# RPi-HAT_BUS-Controller_V0_9b.net
KiCad netlist of a schematic drawn in EAGLE
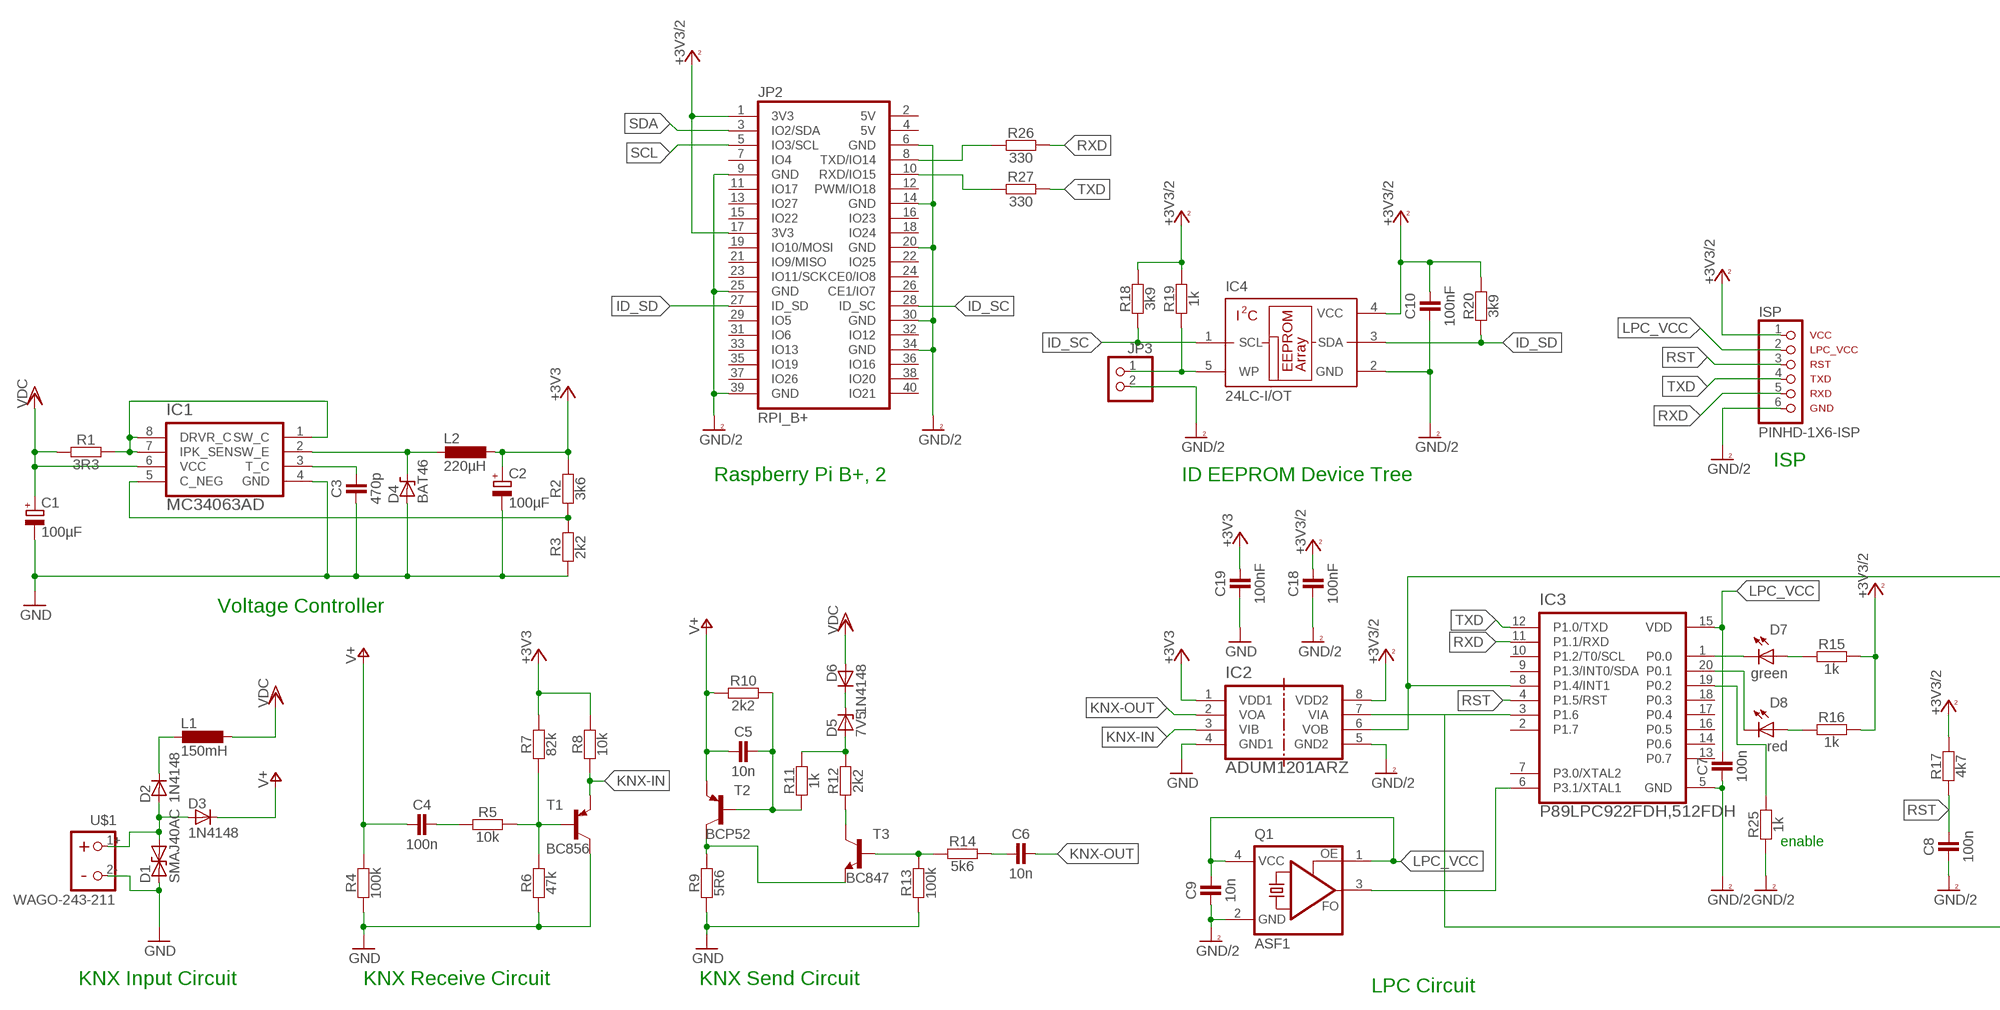
[diagram p0: schematic, sheet 1, part 1 of 2]
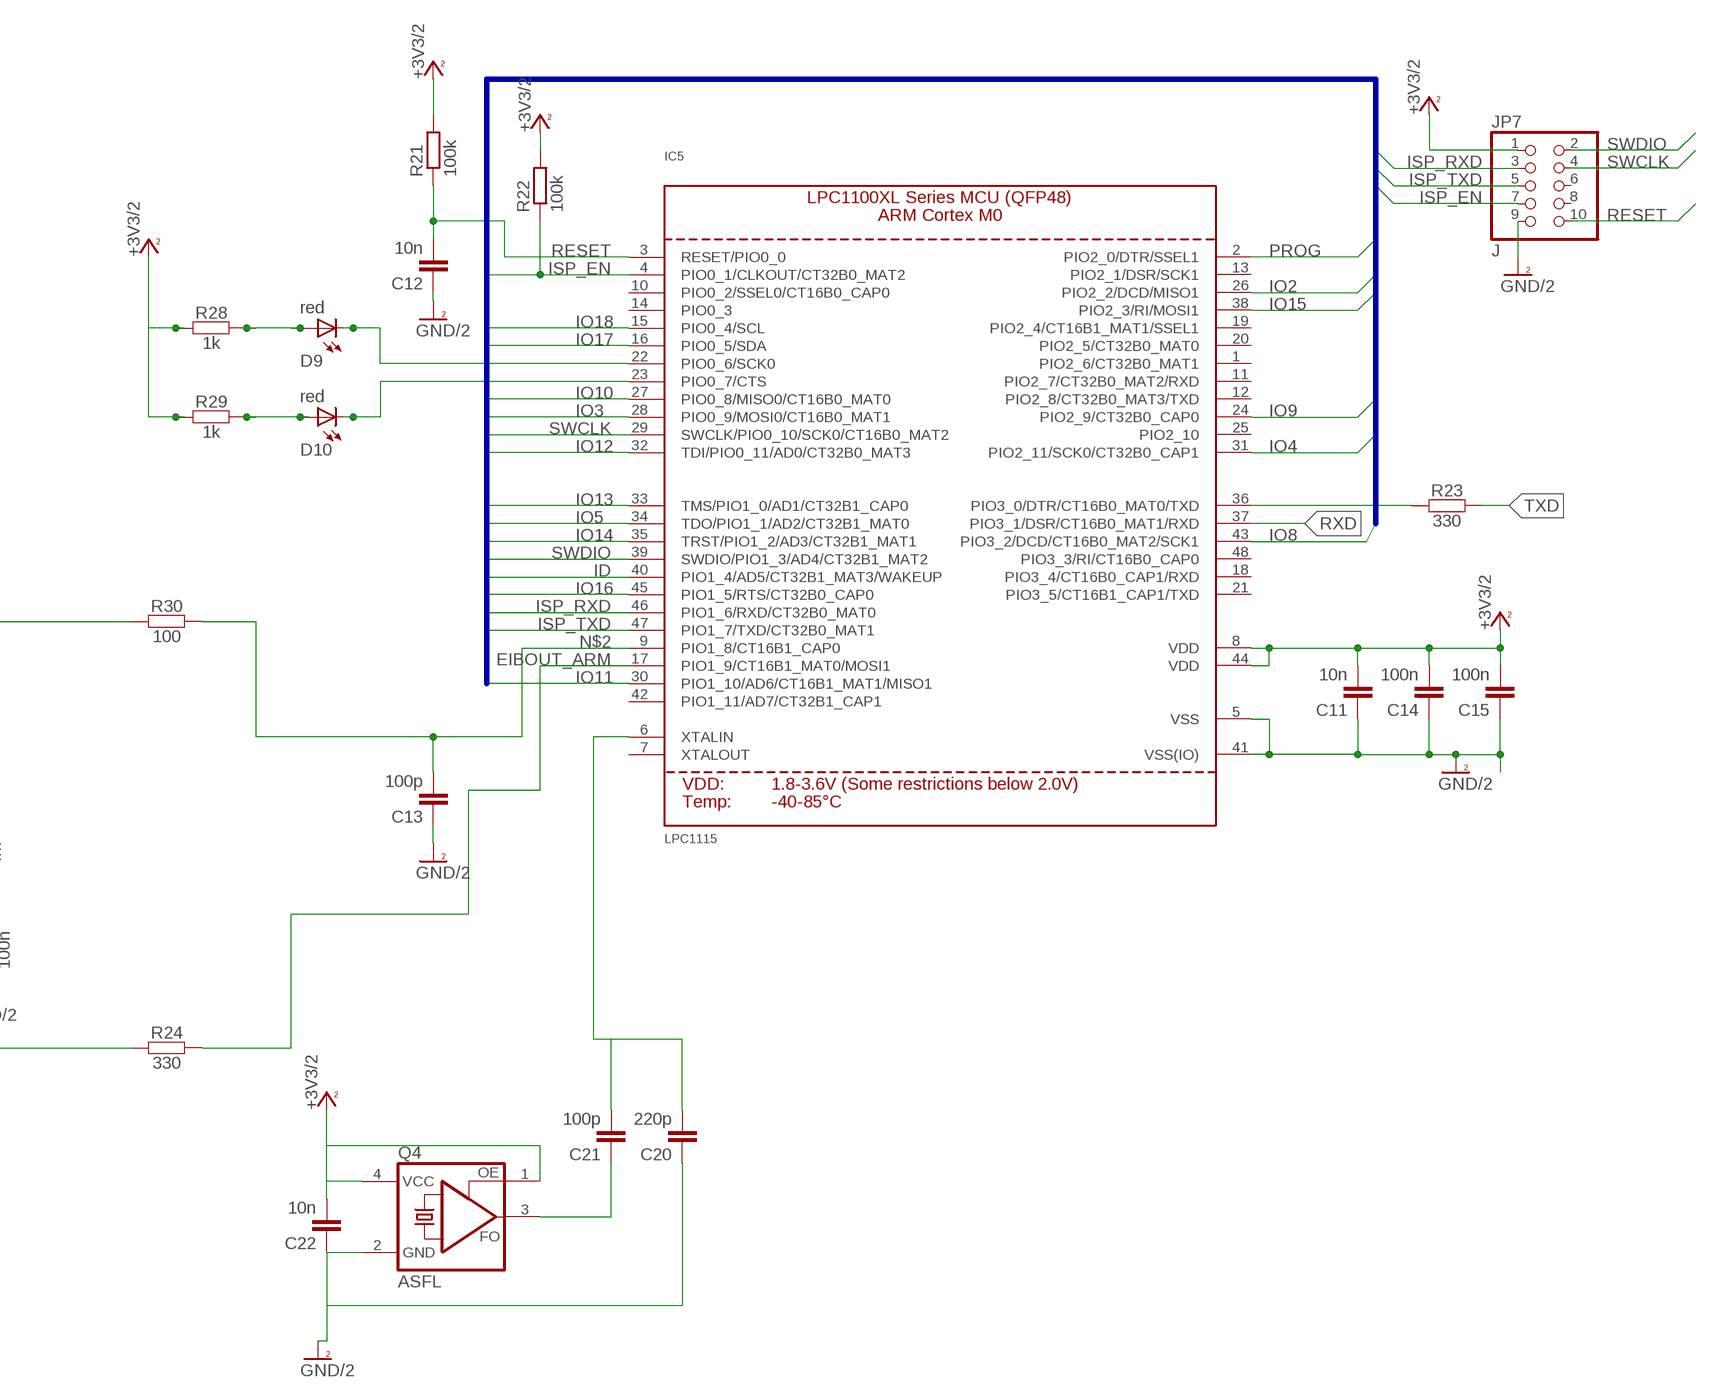
[diagram p1: schematic, sheet 1, part 2 of 2]

(export (version "E")
  (design (tool "Eeschema 10.0.6"))
  (components
    (comp (ref "C1")
      (value "100µF")
      (footprint "eagle-import:PANASONIC_D")
      (libsource (lib "eagle-import") (part "100µF,35V"))
    )
    (comp (ref "C2")
      (value "100µF")
      (footprint "eagle-import:PANASONIC_C")
      (libsource (lib "eagle-import") (part "100µF,6.3V"))
    )
    (comp (ref "C3")
      (value "470p")
      (footprint "eagle-import:R1206")
      (libsource (lib "eagle-import") (part "CAPACITORC1206"))
    )
    (comp (ref "C4")
      (value "100n")
      (footprint "eagle-import:R1206")
      (libsource (lib "eagle-import") (part "CAPACITORC1206"))
    )
    (comp (ref "C5")
      (value "10n")
      (footprint "eagle-import:R1206")
      (libsource (lib "eagle-import") (part "CAPACITORC1206"))
    )
    (comp (ref "C6")
      (value "10n")
      (footprint "eagle-import:R1206")
      (libsource (lib "eagle-import") (part "CAPACITORC1206"))
    )
    (comp (ref "C7")
      (value "100n")
      (footprint "eagle-import:R1206")
      (libsource (lib "eagle-import") (part "CAPACITORC1206"))
    )
    (comp (ref "C8")
      (value "100n")
      (footprint "eagle-import:R1206")
      (libsource (lib "eagle-import") (part "CAPACITORC1206"))
    )
    (comp (ref "C9")
      (value "10n")
      (footprint "eagle-import:R1206")
      (libsource (lib "eagle-import") (part "CAPACITORC1206"))
    )
    (comp (ref "C10")
      (value "100nF")
      (footprint "eagle-import:R1206")
      (libsource (lib "eagle-import") (part "CAPACITORC1206"))
    )
    (comp (ref "C11")
      (value "10n")
      (footprint "eagle-import:C1206")
      (libsource (lib "eagle-import") (part "C-EUC1206"))
    )
    (comp (ref "C12")
      (value "10n")
      (footprint "eagle-import:C1206")
      (libsource (lib "eagle-import") (part "C-EUC1206"))
    )
    (comp (ref "C13")
      (value "100p")
      (footprint "eagle-import:C1206")
      (libsource (lib "eagle-import") (part "C-EUC1206"))
    )
    (comp (ref "C14")
      (value "100n")
      (footprint "eagle-import:C1206")
      (libsource (lib "eagle-import") (part "C-EUC1206"))
    )
    (comp (ref "C15")
      (value "100n")
      (footprint "eagle-import:C1206")
      (libsource (lib "eagle-import") (part "C-EUC1206"))
    )
    (comp (ref "C18")
      (value "100nF")
      (footprint "eagle-import:R1206")
      (libsource (lib "eagle-import") (part "CAPACITORC1206"))
    )
    (comp (ref "C19")
      (value "100nF")
      (footprint "eagle-import:R1206")
      (libsource (lib "eagle-import") (part "CAPACITORC1206"))
    )
    (comp (ref "C20")
      (value "220p")
      (footprint "eagle-import:C1206")
      (libsource (lib "eagle-import") (part "C-EUC1206"))
    )
    (comp (ref "C21")
      (value "100p")
      (footprint "eagle-import:C1206")
      (libsource (lib "eagle-import") (part "C-EUC1206"))
    )
    (comp (ref "C22")
      (value "10n")
      (footprint "eagle-import:C1206")
      (libsource (lib "eagle-import") (part "C-EUC1206"))
    )
    (comp (ref "D1")
      (value "SMAJ40AC")
      (footprint "eagle-import:DO-214AC")
      (libsource (lib "eagle-import") (part "SMAJ40AC"))
    )
    (comp (ref "D2")
      (value "1N4148")
      (footprint "eagle-import:MINIMELF")
      (libsource (lib "eagle-import") (part "1N4148MINIMELF"))
    )
    (comp (ref "D3")
      (value "1N4148")
      (footprint "eagle-import:MINIMELF")
      (libsource (lib "eagle-import") (part "1N4148MINIMELF"))
    )
    (comp (ref "D4")
      (value "BAT46")
      (footprint "eagle-import:MINIMELF")
      (libsource (lib "eagle-import") (part "BAT46"))
    )
    (comp (ref "D5")
      (value "7V5")
      (footprint "eagle-import:MINIMELF")
      (libsource (lib "eagle-import") (part "Z-DIODE"))
    )
    (comp (ref "D6")
      (value "1N4148")
      (footprint "eagle-import:MINIMELF")
      (libsource (lib "eagle-import") (part "Diode_for_Selfbus-Projects_1N4148MINIMELF"))
    )
    (comp (ref "D7")
      (value "green")
      (footprint "eagle-import:CHIPLED_1206")
      (libsource (lib "eagle-import") (part "LED1206"))
    )
    (comp (ref "D8")
      (value "red")
      (footprint "eagle-import:CHIPLED_1206")
      (libsource (lib "eagle-import") (part "LED1206"))
    )
    (comp (ref "D9")
      (value "red")
      (footprint "eagle-import:CHIPLED_1206")
      (libsource (lib "eagle-import") (part "LED1206"))
    )
    (comp (ref "D10")
      (value "red")
      (footprint "eagle-import:CHIPLED_1206")
      (libsource (lib "eagle-import") (part "LED1206"))
    )
    (comp (ref "IC1")
      (value "MC34063AD")
      (footprint "eagle-import:SOIC127P600X175-8N")
      (libsource (lib "eagle-import") (part "MC34063AD"))
    )
    (comp (ref "IC2")
      (value "ADUM1201ARZ")
      (footprint "eagle-import:SOIC127P600X175-8N")
      (libsource (lib "eagle-import") (part "ADUM1201ARZ"))
    )
    (comp (ref "IC3")
      (value "P89LPC922FDH,512FDH")
      (footprint "eagle-import:SOP65P640X110-20N")
      (fields (field (name "MPN") "P89LPC922FDH,512"))
      (libsource (lib "eagle-import") (part "P89LPC922FDH,512FDH"))
    )
    (comp (ref "IC4")
      (value "24LC-I/OT")
      (footprint "eagle-import:SOT23-5")
      (libsource (lib "eagle-import") (part "24LC-I/OT"))
    )
    (comp (ref "IC5")
      (value "LPC1115")
      (footprint "eagle-import:LQFP48")
      (libsource (lib "eagle-import") (part "LPC1113/4/5_QFP48_XLSERIES"))
    )
    (comp (ref "ISP")
      (value "PINHD-1X6-ISP")
      (footprint "eagle-import:1X06")
      (libsource (lib "eagle-import") (part "PINHD-1X6-ISP"))
    )
    (comp (ref "JP2")
      (value "RPI_B+")
      (footprint "eagle-import:RPI-B+HAT")
      (libsource (lib "eagle-import") (part "RPI_B+"))
    )
    (comp (ref "JP3")
      (value "PINHD-1X2")
      (footprint "eagle-import:1X02")
      (libsource (lib "eagle-import") (part "PINHD-1X2"))
    )
    (comp (ref "JP7")
      (value "J")
      (footprint "eagle-import:2X05M")
      (libsource (lib "eagle-import") (part "PINHD-2X05_2.00"))
    )
    (comp (ref "L1")
      (value "150mH")
      (footprint "eagle-import:11P-L1")
      (libsource (lib "eagle-import") (part "150MH-L11PL1"))
    )
    (comp (ref "L2")
      (value "220µH")
      (footprint "eagle-import:2200-11.43")
      (libsource (lib "eagle-import") (part "220µH-SMCC11.43"))
    )
    (comp (ref "Q1")
      (value "ASF1")
      (footprint "eagle-import:ASF")
      (libsource (lib "eagle-import") (part "ASF1"))
    )
    (comp (ref "Q4")
      (value "ASFL")
      (footprint "eagle-import:ASF")
      (fields (field (name "MPN") "ASFLM1-50.000MHZ-C-T"))
      (libsource (lib "eagle-import") (part "crystal_ASFL"))
    )
    (comp (ref "R1")
      (value "3R3")
      (footprint "eagle-import:R1206")
      (libsource (lib "eagle-import") (part "RESISTORR1206"))
    )
    (comp (ref "R2")
      (value "3k6")
      (footprint "eagle-import:R1206")
      (libsource (lib "eagle-import") (part "RESISTORR1206"))
    )
    (comp (ref "R3")
      (value "2k2")
      (footprint "eagle-import:R1206")
      (libsource (lib "eagle-import") (part "RESISTORR1206"))
    )
    (comp (ref "R4")
      (value "100k")
      (footprint "eagle-import:R1206")
      (libsource (lib "eagle-import") (part "RESISTORR1206"))
    )
    (comp (ref "R5")
      (value "10k")
      (footprint "eagle-import:R1206")
      (libsource (lib "eagle-import") (part "RESISTORR1206"))
    )
    (comp (ref "R6")
      (value "47k")
      (footprint "eagle-import:R1206")
      (libsource (lib "eagle-import") (part "RESISTORR1206"))
    )
    (comp (ref "R7")
      (value "82k")
      (footprint "eagle-import:R1206")
      (libsource (lib "eagle-import") (part "RESISTORR1206"))
    )
    (comp (ref "R8")
      (value "10k")
      (footprint "eagle-import:R1206")
      (libsource (lib "eagle-import") (part "RESISTORR1206"))
    )
    (comp (ref "R9")
      (value "5R6")
      (footprint "eagle-import:R1206")
      (libsource (lib "eagle-import") (part "RESISTORR1206"))
    )
    (comp (ref "R10")
      (value "2k2")
      (footprint "eagle-import:R1206")
      (libsource (lib "eagle-import") (part "RESISTORR1206"))
    )
    (comp (ref "R11")
      (value "1k")
      (footprint "eagle-import:R1206")
      (libsource (lib "eagle-import") (part "RESISTORR1206"))
    )
    (comp (ref "R12")
      (value "2k2")
      (footprint "eagle-import:R1206")
      (libsource (lib "eagle-import") (part "RESISTORR1206"))
    )
    (comp (ref "R13")
      (value "100k")
      (footprint "eagle-import:R1206")
      (libsource (lib "eagle-import") (part "RESISTORR1206"))
    )
    (comp (ref "R14")
      (value "5k6")
      (footprint "eagle-import:R1206")
      (libsource (lib "eagle-import") (part "RESISTORR1206"))
    )
    (comp (ref "R15")
      (value "1k")
      (footprint "eagle-import:R1206")
      (libsource (lib "eagle-import") (part "RESISTORR1206"))
    )
    (comp (ref "R16")
      (value "1k")
      (footprint "eagle-import:R1206")
      (libsource (lib "eagle-import") (part "RESISTORR1206"))
    )
    (comp (ref "R17")
      (value "4k7")
      (footprint "eagle-import:R1206")
      (libsource (lib "eagle-import") (part "RESISTORR1206"))
    )
    (comp (ref "R18")
      (value "3k9")
      (footprint "eagle-import:R1206")
      (libsource (lib "eagle-import") (part "RESISTORR1206"))
    )
    (comp (ref "R19")
      (value "1k")
      (footprint "eagle-import:R1206")
      (libsource (lib "eagle-import") (part "RESISTORR1206"))
    )
    (comp (ref "R20")
      (value "3k9")
      (footprint "eagle-import:R1206")
      (libsource (lib "eagle-import") (part "RESISTORR1206"))
    )
    (comp (ref "R21")
      (value "100k")
      (footprint "eagle-import:R1206")
      (libsource (lib "eagle-import") (part "R-EU_R1206"))
    )
    (comp (ref "R22")
      (value "100k")
      (footprint "eagle-import:R1206")
      (libsource (lib "eagle-import") (part "R-EU_R1206"))
    )
    (comp (ref "R23")
      (value "330")
      (footprint "eagle-import:R1206")
      (libsource (lib "eagle-import") (part "RESISTORR1206"))
    )
    (comp (ref "R24")
      (value "330")
      (footprint "eagle-import:R1206")
      (libsource (lib "eagle-import") (part "RESISTORR1206"))
    )
    (comp (ref "R25")
      (value "1k")
      (footprint "eagle-import:R1206")
      (libsource (lib "eagle-import") (part "RESISTORR1206"))
    )
    (comp (ref "R26")
      (value "330")
      (footprint "eagle-import:R1206")
      (libsource (lib "eagle-import") (part "RESISTORR1206"))
    )
    (comp (ref "R27")
      (value "330")
      (footprint "eagle-import:R1206")
      (libsource (lib "eagle-import") (part "RESISTORR1206"))
    )
    (comp (ref "R28")
      (value "1k")
      (footprint "eagle-import:R1206")
      (libsource (lib "eagle-import") (part "RESISTORR1206"))
    )
    (comp (ref "R29")
      (value "1k")
      (footprint "eagle-import:R1206")
      (libsource (lib "eagle-import") (part "RESISTORR1206"))
    )
    (comp (ref "R30")
      (value "100")
      (footprint "eagle-import:R1206")
      (libsource (lib "eagle-import") (part "RESISTORR1206"))
    )
    (comp (ref "T1")
      (value "BC856")
      (footprint "eagle-import:SOT23")
      (libsource (lib "eagle-import") (part "PNPBC856"))
    )
    (comp (ref "T2")
      (value "BCP52")
      (footprint "eagle-import:SOT223")
      (libsource (lib "eagle-import") (part "PNPBCP52"))
    )
    (comp (ref "T3")
      (value "BC847")
      (footprint "eagle-import:SOT23")
      (libsource (lib "eagle-import") (part "NPN-BC847"))
    )
    (comp (ref "U$1")
      (value "WAGO-243-211")
      (footprint "eagle-import:WAGO-243-211")
      (libsource (lib "eagle-import") (part "WAGO-243-211"))
    )
  )
  (nets
    (net (code "1") (name "+3V3") (class "Default")
      (node (ref "C19") (pin "2") (pinfunction "2_2") (pintype "passive"))
      (node (ref "C2") (pin "+") (pinfunction "+_+") (pintype "passive"))
      (node (ref "IC2") (pin "1") (pinfunction "VDD1_1") (pintype "power_in"))
      (node (ref "L2") (pin "1") (pinfunction "1_1") (pintype "passive"))
      (node (ref "R2") (pin "2") (pinfunction "2_2") (pintype "passive"))
      (node (ref "R7") (pin "2") (pinfunction "2_2") (pintype "passive"))
      (node (ref "R8") (pin "2") (pinfunction "2_2") (pintype "passive"))
    )
    (net (code "2") (name "+3V3{slash}2") (class "Default")
      (node (ref "C10") (pin "2") (pinfunction "2_2") (pintype "passive"))
      (node (ref "C11") (pin "2") (pinfunction "2_2") (pintype "passive"))
      (node (ref "C14") (pin "2") (pinfunction "2_2") (pintype "passive"))
      (node (ref "C15") (pin "2") (pinfunction "2_2") (pintype "passive"))
      (node (ref "C18") (pin "2") (pinfunction "2_2") (pintype "passive"))
      (node (ref "C22") (pin "2") (pinfunction "2_2") (pintype "passive"))
      (node (ref "IC2") (pin "8") (pinfunction "VDD2_8") (pintype "power_in"))
      (node (ref "IC4") (pin "4") (pinfunction "VCC_4") (pintype "power_in"))
      (node (ref "IC5") (pin "44") (pinfunction "VDD_44") (pintype "power_in"))
      (node (ref "IC5") (pin "8") (pinfunction "VDD_8") (pintype "power_in"))
      (node (ref "ISP") (pin "1") (pinfunction "1_1") (pintype "passive"))
      (node (ref "JP2") (pin "1") (pinfunction "3V3_1") (pintype "passive"))
      (node (ref "JP2") (pin "17") (pinfunction "3V3_17") (pintype "passive"))
      (node (ref "JP7") (pin "1") (pinfunction "1_1") (pintype "passive"))
      (node (ref "Q4") (pin "1") (pinfunction "OE_1") (pintype "input"))
      (node (ref "Q4") (pin "4") (pinfunction "VCC_4") (pintype "power_in"))
      (node (ref "R15") (pin "2") (pinfunction "2_2") (pintype "passive"))
      (node (ref "R16") (pin "2") (pinfunction "2_2") (pintype "passive"))
      (node (ref "R17") (pin "2") (pinfunction "2_2") (pintype "passive"))
      (node (ref "R18") (pin "2") (pinfunction "2_2") (pintype "passive"))
      (node (ref "R19") (pin "2") (pinfunction "2_2") (pintype "passive"))
      (node (ref "R20") (pin "2") (pinfunction "2_2") (pintype "passive"))
      (node (ref "R21") (pin "2") (pinfunction "2_2") (pintype "passive"))
      (node (ref "R22") (pin "2") (pinfunction "2_2") (pintype "passive"))
      (node (ref "R28") (pin "1") (pinfunction "1_1") (pintype "passive"))
      (node (ref "R29") (pin "1") (pinfunction "1_1") (pintype "passive"))
    )
    (net (code "3") (name "/EIBOUT_ARM") (class "Default")
      (node (ref "IC5") (pin "17") (pinfunction "PIO1_9/CT16B1_MAT0/MOSI1_17") (pintype "bidirectional"))
      (node (ref "R24") (pin "2") (pinfunction "2_2") (pintype "passive"))
    )
    (net (code "4") (name "/ID") (class "Default")
      (node (ref "IC5") (pin "40") (pinfunction "PIO1_4/AD5/CT32B1_MAT3/WAKEUP_40") (pintype "bidirectional"))
    )
    (net (code "5") (name "/IO2") (class "Default")
      (node (ref "IC5") (pin "26") (pinfunction "PIO2_2/DCD/MISO1_26") (pintype "bidirectional"))
    )
    (net (code "6") (name "/IO3") (class "Default")
      (node (ref "IC5") (pin "28") (pinfunction "PIO0_9/MOSI0/CT16B0_MAT1_28") (pintype "bidirectional"))
    )
    (net (code "7") (name "/IO4") (class "Default")
      (node (ref "IC5") (pin "31") (pinfunction "PIO2_11/SCK0/CT32B0_CAP1_31") (pintype "bidirectional"))
    )
    (net (code "8") (name "/IO5") (class "Default")
      (node (ref "IC5") (pin "34") (pinfunction "TDO/PIO1_1/AD2/CT32B1_MAT0_34") (pintype "bidirectional"))
    )
    (net (code "9") (name "/IO8") (class "Default")
      (node (ref "IC5") (pin "43") (pinfunction "PIO3_2/DCD/CT16B0_MAT2/SCK1_43") (pintype "bidirectional"))
    )
    (net (code "10") (name "/IO9") (class "Default")
      (node (ref "IC5") (pin "24") (pinfunction "PIO2_9/CT32B0_CAP0_24") (pintype "bidirectional"))
    )
    (net (code "11") (name "/IO10") (class "Default")
      (node (ref "IC5") (pin "27") (pinfunction "PIO0_8/MISO0/CT16B0_MAT0_27") (pintype "bidirectional"))
    )
    (net (code "12") (name "/IO11") (class "Default")
      (node (ref "IC5") (pin "30") (pinfunction "PIO1_10/AD6/CT16B1_MAT1/MISO1_30") (pintype "bidirectional"))
    )
    (net (code "13") (name "/IO12") (class "Default")
      (node (ref "IC5") (pin "32") (pinfunction "TDI/PIO0_11/AD0/CT32B0_MAT3_32") (pintype "bidirectional"))
    )
    (net (code "14") (name "/IO13") (class "Default")
      (node (ref "IC5") (pin "33") (pinfunction "TMS/PIO1_0/AD1/CT32B1_CAP0_33") (pintype "bidirectional"))
    )
    (net (code "15") (name "/IO14") (class "Default")
      (node (ref "IC5") (pin "35") (pinfunction "TRST/PIO1_2/AD3/CT32B1_MAT1_35") (pintype "bidirectional"))
    )
    (net (code "16") (name "/IO15") (class "Default")
      (node (ref "IC5") (pin "38") (pinfunction "PIO2_3/RI/MOSI1_38") (pintype "bidirectional"))
    )
    (net (code "17") (name "/IO16") (class "Default")
      (node (ref "IC5") (pin "45") (pinfunction "PIO1_5/RTS/CT32B0_CAP0_45") (pintype "bidirectional"))
    )
    (net (code "18") (name "/IO17") (class "Default")
      (node (ref "IC5") (pin "16") (pinfunction "PIO0_5/SDA_16") (pintype "bidirectional"))
    )
    (net (code "19") (name "/IO18") (class "Default")
      (node (ref "IC5") (pin "15") (pinfunction "PIO0_4/SCL_15") (pintype "bidirectional"))
    )
    (net (code "20") (name "/ISP_EN") (class "Default")
      (node (ref "IC5") (pin "4") (pinfunction "PIO0_1/CLKOUT/CT32B0_MAT2_4") (pintype "bidirectional"))
      (node (ref "JP7") (pin "7") (pinfunction "7_7") (pintype "passive"))
      (node (ref "R22") (pin "1") (pinfunction "1_1") (pintype "passive"))
    )
    (net (code "21") (name "/ISP_RXD") (class "Default")
      (node (ref "IC5") (pin "46") (pinfunction "PIO1_6/RXD/CT32B0_MAT0_46") (pintype "bidirectional"))
      (node (ref "JP7") (pin "3") (pinfunction "3_3") (pintype "passive"))
    )
    (net (code "22") (name "/ISP_TXD") (class "Default")
      (node (ref "IC5") (pin "47") (pinfunction "PIO1_7/TXD/CT32B0_MAT1_47") (pintype "bidirectional"))
      (node (ref "JP7") (pin "5") (pinfunction "5_5") (pintype "passive"))
    )
    (net (code "23") (name "/N$2") (class "Default")
      (node (ref "C13") (pin "2") (pinfunction "2_2") (pintype "passive"))
      (node (ref "IC5") (pin "9") (pinfunction "PIO1_8/CT16B1_CAP0_9") (pintype "bidirectional"))
      (node (ref "R30") (pin "2") (pinfunction "2_2") (pintype "passive"))
    )
    (net (code "24") (name "/PROG") (class "Default")
      (node (ref "IC5") (pin "2") (pinfunction "PIO2_0/DTR/SSEL1_2") (pintype "bidirectional"))
    )
    (net (code "25") (name "/RESET") (class "Default")
      (node (ref "C12") (pin "2") (pinfunction "2_2") (pintype "passive"))
      (node (ref "IC5") (pin "3") (pinfunction "RESET/PIO0_0_3") (pintype "bidirectional"))
      (node (ref "JP7") (pin "10") (pinfunction "10_10") (pintype "passive"))
      (node (ref "R21") (pin "1") (pinfunction "1_1") (pintype "passive"))
    )
    (net (code "26") (name "/SWCLK") (class "Default")
      (node (ref "IC5") (pin "29") (pinfunction "SWCLK/PIO0_10/SCK0/CT16B0_MAT2_29") (pintype "bidirectional"))
      (node (ref "JP7") (pin "4") (pinfunction "4_4") (pintype "passive"))
    )
    (net (code "27") (name "/SWDIO") (class "Default")
      (node (ref "IC5") (pin "39") (pinfunction "SWDIO/PIO1_3/AD4/CT32B1_MAT2_39") (pintype "bidirectional"))
      (node (ref "JP7") (pin "2") (pinfunction "2_2") (pintype "passive"))
    )
    (net (code "28") (name "GND") (class "Default")
      (node (ref "C1") (pin "-") (pinfunction "-_-") (pintype "passive"))
      (node (ref "C19") (pin "1") (pinfunction "1_1") (pintype "passive"))
      (node (ref "C2") (pin "-") (pinfunction "-_-") (pintype "passive"))
      (node (ref "C3") (pin "1") (pinfunction "1_1") (pintype "passive"))
      (node (ref "D1") (pin "A") (pinfunction "A_A") (pintype "passive"))
      (node (ref "D4") (pin "A") (pinfunction "A_A") (pintype "passive"))
      (node (ref "IC1") (pin "4") (pinfunction "GND_4") (pintype "passive"))
      (node (ref "IC2") (pin "4") (pinfunction "GND1_4") (pintype "passive"))
      (node (ref "R13") (pin "1") (pinfunction "1_1") (pintype "passive"))
      (node (ref "R3") (pin "1") (pinfunction "1_1") (pintype "passive"))
      (node (ref "R4") (pin "1") (pinfunction "1_1") (pintype "passive"))
      (node (ref "R6") (pin "1") (pinfunction "1_1") (pintype "passive"))
      (node (ref "R9") (pin "1") (pinfunction "1_1") (pintype "passive"))
      (node (ref "T1") (pin "3") (pinfunction "C_3") (pintype "passive"))
      (node (ref "U$1") (pin "2-") (pinfunction "2-_2-") (pintype "passive"))
    )
    (net (code "29") (name "GND{slash}2") (class "Default")
      (node (ref "C10") (pin "1") (pinfunction "1_1") (pintype "passive"))
      (node (ref "C11") (pin "1") (pinfunction "1_1") (pintype "passive"))
      (node (ref "C12") (pin "1") (pinfunction "1_1") (pintype "passive"))
      (node (ref "C13") (pin "1") (pinfunction "1_1") (pintype "passive"))
      (node (ref "C14") (pin "1") (pinfunction "1_1") (pintype "passive"))
      (node (ref "C15") (pin "1") (pinfunction "1_1") (pintype "passive"))
      (node (ref "C18") (pin "1") (pinfunction "1_1") (pintype "passive"))
      (node (ref "C20") (pin "1") (pinfunction "1_1") (pintype "passive"))
      (node (ref "C22") (pin "1") (pinfunction "1_1") (pintype "passive"))
      (node (ref "C7") (pin "1") (pinfunction "1_1") (pintype "passive"))
      (node (ref "C8") (pin "1") (pinfunction "1_1") (pintype "passive"))
      (node (ref "C9") (pin "1") (pinfunction "1_1") (pintype "passive"))
      (node (ref "IC2") (pin "5") (pinfunction "GND2_5") (pintype "passive"))
      (node (ref "IC3") (pin "5") (pinfunction "GND_5") (pintype "passive"))
      (node (ref "IC4") (pin "2") (pinfunction "GND_2") (pintype "power_in"))
      (node (ref "IC5") (pin "41") (pinfunction "VSS(IO)_41") (pintype "power_in"))
      (node (ref "IC5") (pin "5") (pinfunction "VSS_5") (pintype "power_in"))
      (node (ref "ISP") (pin "6") (pinfunction "6_6") (pintype "passive"))
      (node (ref "JP2") (pin "14") (pinfunction "GND_14") (pintype "passive"))
      (node (ref "JP2") (pin "20") (pinfunction "GND_20") (pintype "passive"))
      (node (ref "JP2") (pin "25") (pinfunction "GND_25") (pintype "passive"))
      (node (ref "JP2") (pin "30") (pinfunction "GND_30") (pintype "bidirectional"))
      (node (ref "JP2") (pin "34") (pinfunction "GND_34") (pintype "bidirectional"))
      (node (ref "JP2") (pin "39") (pinfunction "GND_39") (pintype "bidirectional"))
      (node (ref "JP2") (pin "6") (pinfunction "GND_6") (pintype "passive"))
      (node (ref "JP2") (pin "9") (pinfunction "GND_9") (pintype "passive"))
      (node (ref "JP3") (pin "2") (pinfunction "2_2") (pintype "passive"))
      (node (ref "JP7") (pin "9") (pinfunction "9_9") (pintype "passive"))
      (node (ref "Q1") (pin "2") (pinfunction "GND_2") (pintype "power_in"))
      (node (ref "Q4") (pin "2") (pinfunction "GND_2") (pintype "power_in"))
      (node (ref "R25") (pin "1") (pinfunction "1_1") (pintype "passive"))
    )
    (net (code "30") (name "ID_SC") (class "Default")
      (node (ref "IC4") (pin "1") (pinfunction "SCL_1") (pintype "bidirectional"))
      (node (ref "JP2") (pin "28") (pinfunction "ID_SC_28") (pintype "bidirectional"))
      (node (ref "R18") (pin "1") (pinfunction "1_1") (pintype "passive"))
    )
    (net (code "31") (name "ID_SD") (class "Default")
      (node (ref "IC4") (pin "3") (pinfunction "SDA_3") (pintype "bidirectional"))
      (node (ref "JP2") (pin "27") (pinfunction "ID_SD_27") (pintype "bidirectional"))
      (node (ref "R20") (pin "1") (pinfunction "1_1") (pintype "passive"))
    )
    (net (code "32") (name "KNX-IN") (class "Default")
      (node (ref "IC2") (pin "3") (pinfunction "VIB_3") (pintype "input"))
      (node (ref "R8") (pin "1") (pinfunction "1_1") (pintype "passive"))
      (node (ref "T1") (pin "2") (pinfunction "E_2") (pintype "passive"))
    )
    (net (code "33") (name "KNX-OUT") (class "Default")
      (node (ref "C6") (pin "2") (pinfunction "2_2") (pintype "passive"))
      (node (ref "IC2") (pin "2") (pinfunction "VOA_2") (pintype "output"))
    )
    (net (code "34") (name "LPC_VCC") (class "Default")
      (node (ref "C7") (pin "2") (pinfunction "2_2") (pintype "passive"))
      (node (ref "C9") (pin "2") (pinfunction "2_2") (pintype "passive"))
      (node (ref "IC3") (pin "15") (pinfunction "VDD_15") (pintype "power_in"))
      (node (ref "ISP") (pin "2") (pinfunction "2_2") (pintype "passive"))
      (node (ref "Q1") (pin "1") (pinfunction "OE_1") (pintype "input"))
      (node (ref "Q1") (pin "4") (pinfunction "VCC_4") (pintype "power_in"))
    )
    (net (code "35") (name "Net-(C4-Pad2)") (class "Default")
      (node (ref "C4") (pin "2") (pinfunction "2_2") (pintype "passive"))
      (node (ref "R5") (pin "1") (pinfunction "1_1") (pintype "passive"))
    )
    (net (code "36") (name "Net-(C6-Pad1)") (class "Default")
      (node (ref "C6") (pin "1") (pinfunction "1_1") (pintype "passive"))
      (node (ref "R14") (pin "2") (pinfunction "2_2") (pintype "passive"))
    )
    (net (code "37") (name "Net-(D1-PadC)") (class "Default")
      (node (ref "D1") (pin "C") (pinfunction "C_C") (pintype "passive"))
      (node (ref "D2") (pin "A") (pinfunction "A_A") (pintype "passive"))
      (node (ref "D3") (pin "A") (pinfunction "A_A") (pintype "passive"))
      (node (ref "U$1") (pin "1+") (pinfunction "1+_1+") (pintype "passive"))
    )
    (net (code "38") (name "Net-(D2-PadC)") (class "Default")
      (node (ref "D2") (pin "C") (pinfunction "C_C") (pintype "passive"))
      (node (ref "L1") (pin "2") (pinfunction "2_2") (pintype "passive"))
    )
    (net (code "39") (name "Net-(D5-PadA)") (class "Default")
      (node (ref "D5") (pin "A") (pinfunction "A_A") (pintype "passive"))
      (node (ref "R11") (pin "2") (pinfunction "2_2") (pintype "passive"))
      (node (ref "R12") (pin "2") (pinfunction "2_2") (pintype "passive"))
    )
    (net (code "40") (name "Net-(D5-PadC)") (class "Default")
      (node (ref "D5") (pin "C") (pinfunction "C_C") (pintype "passive"))
      (node (ref "D6") (pin "C") (pinfunction "C_C") (pintype "passive"))
    )
    (net (code "41") (name "Net-(D7-PadA)") (class "Default")
      (node (ref "D7") (pin "A") (pinfunction "A_A") (pintype "passive"))
      (node (ref "R15") (pin "1") (pinfunction "1_1") (pintype "passive"))
    )
    (net (code "42") (name "Net-(D8-PadA)") (class "Default")
      (node (ref "D8") (pin "A") (pinfunction "A_A") (pintype "passive"))
      (node (ref "R16") (pin "1") (pinfunction "1_1") (pintype "passive"))
    )
    (net (code "43") (name "Net-(D9-PadA)") (class "Default")
      (node (ref "D9") (pin "A") (pinfunction "A_A") (pintype "passive"))
      (node (ref "R28") (pin "2") (pinfunction "2_2") (pintype "passive"))
    )
    (net (code "44") (name "Net-(D10-PadA)") (class "Default")
      (node (ref "D10") (pin "A") (pinfunction "A_A") (pintype "passive"))
      (node (ref "R29") (pin "2") (pinfunction "2_2") (pintype "passive"))
    )
    (net (code "45") (name "Net-(IC1-C_NEG)") (class "Default")
      (node (ref "IC1") (pin "5") (pinfunction "C_NEG_5") (pintype "input"))
      (node (ref "R2") (pin "1") (pinfunction "1_1") (pintype "passive"))
      (node (ref "R3") (pin "2") (pinfunction "2_2") (pintype "passive"))
    )
    (net (code "46") (name "Net-(IC1-DRVR_C)") (class "Default")
      (node (ref "IC1") (pin "1") (pinfunction "SW_C_1") (pintype "output"))
      (node (ref "IC1") (pin "7") (pinfunction "IPK_SEN_7") (pintype "input"))
      (node (ref "IC1") (pin "8") (pinfunction "DRVR_C_8") (pintype "input"))
      (node (ref "R1") (pin "2") (pinfunction "2_2") (pintype "passive"))
    )
    (net (code "47") (name "Net-(IC1-SW_E)") (class "Default")
      (node (ref "D4") (pin "C") (pinfunction "C_C") (pintype "passive"))
      (node (ref "IC1") (pin "2") (pinfunction "SW_E_2") (pintype "output"))
      (node (ref "L2") (pin "2") (pinfunction "2_2") (pintype "passive"))
    )
    (net (code "48") (name "Net-(IC1-T_C)") (class "Default")
      (node (ref "C3") (pin "2") (pinfunction "2_2") (pintype "passive"))
      (node (ref "IC1") (pin "3") (pinfunction "T_C_3") (pintype "output"))
    )
    (net (code "49") (name "Net-(IC2-VIA)") (class "Default")
      (node (ref "IC2") (pin "7") (pinfunction "VIA_7") (pintype "input"))
      (node (ref "IC3") (pin "3") (pinfunction "P1.6_3") (pintype "bidirectional"))
      (node (ref "R24") (pin "1") (pinfunction "1_1") (pintype "passive"))
    )
    (net (code "50") (name "Net-(IC2-VOB)") (class "Default")
      (node (ref "IC2") (pin "6") (pinfunction "VOB_6") (pintype "output"))
      (node (ref "IC3") (pin "8") (pinfunction "P1.4/INT1_8") (pintype "bidirectional"))
      (node (ref "R30") (pin "1") (pinfunction "1_1") (pintype "passive"))
    )
    (net (code "51") (name "Net-(IC3-P0.0)") (class "Default")
      (node (ref "D7") (pin "C") (pinfunction "C_C") (pintype "passive"))
      (node (ref "IC3") (pin "1") (pinfunction "P0.0_1") (pintype "bidirectional"))
    )
    (net (code "52") (name "Net-(IC3-P0.1)") (class "Default")
      (node (ref "D8") (pin "C") (pinfunction "C_C") (pintype "passive"))
      (node (ref "IC3") (pin "20") (pinfunction "P0.1_20") (pintype "bidirectional"))
    )
    (net (code "53") (name "Net-(IC3-P0.2)") (class "Default")
      (node (ref "IC3") (pin "19") (pinfunction "P0.2_19") (pintype "bidirectional"))
      (node (ref "R25") (pin "2") (pinfunction "2_2") (pintype "passive"))
    )
    (net (code "54") (name "Net-(IC3-P3.1{slash}XTAL1)") (class "Default")
      (node (ref "IC3") (pin "6") (pinfunction "P3.1/XTAL1_6") (pintype "bidirectional"))
      (node (ref "Q1") (pin "3") (pinfunction "FO_3") (pintype "output"))
    )
    (net (code "55") (name "Net-(IC4-WP)") (class "Default")
      (node (ref "IC4") (pin "5") (pinfunction "WP_5") (pintype "bidirectional"))
      (node (ref "JP3") (pin "1") (pinfunction "1_1") (pintype "passive"))
      (node (ref "R19") (pin "1") (pinfunction "1_1") (pintype "passive"))
    )
    (net (code "56") (name "Net-(IC5-PIO0_6{slash}SCK0)") (class "Default")
      (node (ref "D9") (pin "C") (pinfunction "C_C") (pintype "passive"))
      (node (ref "IC5") (pin "22") (pinfunction "PIO0_6/SCK0_22") (pintype "bidirectional"))
    )
    (net (code "57") (name "Net-(IC5-PIO0_7{slash}CTS)") (class "Default")
      (node (ref "D10") (pin "C") (pinfunction "C_C") (pintype "passive"))
      (node (ref "IC5") (pin "23") (pinfunction "PIO0_7/CTS_23") (pintype "bidirectional"))
    )
    (net (code "58") (name "Net-(IC5-PIO3_0{slash}DTR{slash}CT16B0_MAT0{slash}TXD)") (class "Default")
      (node (ref "IC5") (pin "36") (pinfunction "PIO3_0/DTR/CT16B0_MAT0/TXD_36") (pintype "bidirectional"))
      (node (ref "R23") (pin "1") (pinfunction "1_1") (pintype "passive"))
    )
    (net (code "59") (name "Net-(IC5-XTALIN)") (class "Default")
      (node (ref "C20") (pin "2") (pinfunction "2_2") (pintype "passive"))
      (node (ref "C21") (pin "2") (pinfunction "2_2") (pintype "passive"))
      (node (ref "IC5") (pin "6") (pinfunction "XTALIN_6") (pintype "input"))
    )
    (net (code "60") (name "Net-(JP2-RXD{slash}IO15)") (class "Default")
      (node (ref "JP2") (pin "10") (pinfunction "RXD/IO15_10") (pintype "passive"))
      (node (ref "R27") (pin "1") (pinfunction "1_1") (pintype "passive"))
    )
    (net (code "61") (name "Net-(JP2-TXD{slash}IO14)") (class "Default")
      (node (ref "JP2") (pin "8") (pinfunction "TXD/IO14_8") (pintype "passive"))
      (node (ref "R26") (pin "1") (pinfunction "1_1") (pintype "passive"))
    )
    (net (code "62") (name "Net-(Q4-FO)") (class "Default")
      (node (ref "C21") (pin "1") (pinfunction "1_1") (pintype "passive"))
      (node (ref "Q4") (pin "3") (pinfunction "FO_3") (pintype "output"))
    )
    (net (code "63") (name "Net-(T1-B)") (class "Default")
      (node (ref "R5") (pin "2") (pinfunction "2_2") (pintype "passive"))
      (node (ref "R6") (pin "2") (pinfunction "2_2") (pintype "passive"))
      (node (ref "R7") (pin "1") (pinfunction "1_1") (pintype "passive"))
      (node (ref "T1") (pin "1") (pinfunction "B_1") (pintype "passive"))
    )
    (net (code "64") (name "Net-(T2-B)") (class "Default")
      (node (ref "C5") (pin "2") (pinfunction "2_2") (pintype "passive"))
      (node (ref "R10") (pin "2") (pinfunction "2_2") (pintype "passive"))
      (node (ref "R11") (pin "1") (pinfunction "1_1") (pintype "passive"))
      (node (ref "T2") (pin "1") (pinfunction "B_1") (pintype "passive"))
    )
    (net (code "65") (name "Net-(T3-B)") (class "Default")
      (node (ref "R13") (pin "2") (pinfunction "2_2") (pintype "passive"))
      (node (ref "R14") (pin "1") (pinfunction "1_1") (pintype "passive"))
      (node (ref "T3") (pin "1") (pinfunction "B_1") (pintype "passive"))
    )
    (net (code "66") (name "Net-(T3-C)") (class "Default")
      (node (ref "R12") (pin "1") (pinfunction "1_1") (pintype "passive"))
      (node (ref "T3") (pin "3") (pinfunction "C_3") (pintype "passive"))
    )
    (net (code "67") (name "Net-(T3-E)") (class "Default")
      (node (ref "R9") (pin "2") (pinfunction "2_2") (pintype "passive"))
      (node (ref "T2") (pin "2") (pinfunction "C_2") (pintype "passive"))
      (node (ref "T2") (pin "4") (pinfunction "C_4") (pintype "passive"))
      (node (ref "T3") (pin "2") (pinfunction "E_2") (pintype "passive"))
    )
    (net (code "68") (name "RST") (class "Default")
      (node (ref "C8") (pin "2") (pinfunction "2_2") (pintype "passive"))
      (node (ref "IC3") (pin "4") (pinfunction "P1.5/RST_4") (pintype "input"))
      (node (ref "ISP") (pin "3") (pinfunction "3_3") (pintype "passive"))
      (node (ref "R17") (pin "1") (pinfunction "1_1") (pintype "passive"))
    )
    (net (code "69") (name "RXD") (class "Default")
      (node (ref "IC3") (pin "11") (pinfunction "P1.1/RXD_11") (pintype "bidirectional"))
      (node (ref "IC5") (pin "37") (pinfunction "PIO3_1/DSR/CT16B0_MAT1/RXD_37") (pintype "bidirectional"))
      (node (ref "ISP") (pin "5") (pinfunction "5_5") (pintype "passive"))
      (node (ref "R26") (pin "2") (pinfunction "2_2") (pintype "passive"))
    )
    (net (code "70") (name "SCL") (class "Default")
      (node (ref "JP2") (pin "5") (pinfunction "IO3/SCL_5") (pintype "passive"))
    )
    (net (code "71") (name "SDA") (class "Default")
      (node (ref "JP2") (pin "3") (pinfunction "IO2/SDA_3") (pintype "passive"))
    )
    (net (code "72") (name "TXD") (class "Default")
      (node (ref "IC3") (pin "12") (pinfunction "P1.0/TXD_12") (pintype "bidirectional"))
      (node (ref "ISP") (pin "4") (pinfunction "4_4") (pintype "passive"))
      (node (ref "R23") (pin "2") (pinfunction "2_2") (pintype "passive"))
      (node (ref "R27") (pin "2") (pinfunction "2_2") (pintype "passive"))
    )
    (net (code "73") (name "V+") (class "Default")
      (node (ref "C4") (pin "1") (pinfunction "1_1") (pintype "passive"))
      (node (ref "C5") (pin "1") (pinfunction "1_1") (pintype "passive"))
      (node (ref "D3") (pin "C") (pinfunction "C_C") (pintype "passive"))
      (node (ref "R10") (pin "1") (pinfunction "1_1") (pintype "passive"))
      (node (ref "R4") (pin "2") (pinfunction "2_2") (pintype "passive"))
      (node (ref "T2") (pin "3") (pinfunction "E_3") (pintype "passive"))
    )
    (net (code "74") (name "VDC") (class "Default")
      (node (ref "C1") (pin "+") (pinfunction "+_+") (pintype "passive"))
      (node (ref "D6") (pin "A") (pinfunction "A_A") (pintype "passive"))
      (node (ref "IC1") (pin "6") (pinfunction "VCC_6") (pintype "power_in"))
      (node (ref "L1") (pin "1") (pinfunction "1_1") (pintype "passive"))
      (node (ref "R1") (pin "1") (pinfunction "1_1") (pintype "passive"))
    )
    (net (code "75") (name "unconnected-(IC3-P0.3-Pad18)") (class "Default")
      (node (ref "IC3") (pin "18") (pinfunction "P0.3_18") (pintype "bidirectional"))
    )
    (net (code "76") (name "unconnected-(IC3-P0.4-Pad17)") (class "Default")
      (node (ref "IC3") (pin "17") (pinfunction "P0.4_17") (pintype "bidirectional"))
    )
    (net (code "77") (name "unconnected-(IC3-P0.5-Pad16)") (class "Default")
      (node (ref "IC3") (pin "16") (pinfunction "P0.5_16") (pintype "bidirectional"))
    )
    (net (code "78") (name "unconnected-(IC3-P0.6-Pad14)") (class "Default")
      (node (ref "IC3") (pin "14") (pinfunction "P0.6_14") (pintype "bidirectional"))
    )
    (net (code "79") (name "unconnected-(IC3-P0.7-Pad13)") (class "Default")
      (node (ref "IC3") (pin "13") (pinfunction "P0.7_13") (pintype "passive"))
    )
    (net (code "80") (name "unconnected-(IC3-P1.2{slash}T0{slash}SCL-Pad10)") (class "Default")
      (node (ref "IC3") (pin "10") (pinfunction "P1.2/T0/SCL_10") (pintype "bidirectional"))
    )
    (net (code "81") (name "unconnected-(IC3-P1.3{slash}INT0{slash}SDA-Pad9)") (class "Default")
      (node (ref "IC3") (pin "9") (pinfunction "P1.3/INT0/SDA_9") (pintype "bidirectional"))
    )
    (net (code "82") (name "unconnected-(IC3-P1.7-Pad2)") (class "Default")
      (node (ref "IC3") (pin "2") (pinfunction "P1.7_2") (pintype "bidirectional"))
    )
    (net (code "83") (name "unconnected-(IC3-P3.0{slash}XTAL2-Pad7)") (class "Default")
      (node (ref "IC3") (pin "7") (pinfunction "P3.0/XTAL2_7") (pintype "bidirectional"))
    )
    (net (code "84") (name "unconnected-(IC5-PIO0_2{slash}SSEL0{slash}CT16B0_CAP0-Pad10)") (class "Default")
      (node (ref "IC5") (pin "10") (pinfunction "PIO0_2/SSEL0/CT16B0_CAP0_10") (pintype "bidirectional"))
    )
    (net (code "85") (name "unconnected-(IC5-PIO0_3-Pad14)") (class "Default")
      (node (ref "IC5") (pin "14") (pinfunction "PIO0_3_14") (pintype "bidirectional"))
    )
    (net (code "86") (name "unconnected-(IC5-PIO1_11{slash}AD7{slash}CT32B1_CAP1-Pad42)") (class "Default")
      (node (ref "IC5") (pin "42") (pinfunction "PIO1_11/AD7/CT32B1_CAP1_42") (pintype "bidirectional"))
    )
    (net (code "87") (name "unconnected-(IC5-PIO2_1{slash}DSR{slash}SCK1-Pad13)") (class "Default")
      (node (ref "IC5") (pin "13") (pinfunction "PIO2_1/DSR/SCK1_13") (pintype "bidirectional"))
    )
    (net (code "88") (name "unconnected-(IC5-PIO2_4{slash}CT16B1_MAT1{slash}SSEL1-Pad19)") (class "Default")
      (node (ref "IC5") (pin "19") (pinfunction "PIO2_4/CT16B1_MAT1/SSEL1_19") (pintype "bidirectional"))
    )
    (net (code "89") (name "unconnected-(IC5-PIO2_5{slash}CT32B0_MAT0-Pad20)") (class "Default")
      (node (ref "IC5") (pin "20") (pinfunction "PIO2_5/CT32B0_MAT0_20") (pintype "bidirectional"))
    )
    (net (code "90") (name "unconnected-(IC5-PIO2_6{slash}CT32B0_MAT1-Pad1)") (class "Default")
      (node (ref "IC5") (pin "1") (pinfunction "PIO2_6/CT32B0_MAT1_1") (pintype "bidirectional"))
    )
    (net (code "91") (name "unconnected-(IC5-PIO2_7{slash}CT32B0_MAT2{slash}RXD-Pad11)") (class "Default")
      (node (ref "IC5") (pin "11") (pinfunction "PIO2_7/CT32B0_MAT2/RXD_11") (pintype "bidirectional"))
    )
    (net (code "92") (name "unconnected-(IC5-PIO2_8{slash}CT32B0_MAT3{slash}TXD-Pad12)") (class "Default")
      (node (ref "IC5") (pin "12") (pinfunction "PIO2_8/CT32B0_MAT3/TXD_12") (pintype "bidirectional"))
    )
    (net (code "93") (name "unconnected-(IC5-PIO2_10-Pad25)") (class "Default")
      (node (ref "IC5") (pin "25") (pinfunction "PIO2_10_25") (pintype "bidirectional"))
    )
    (net (code "94") (name "unconnected-(IC5-PIO3_3{slash}RI{slash}CT16B0_CAP0-Pad48)") (class "Default")
      (node (ref "IC5") (pin "48") (pinfunction "PIO3_3/RI/CT16B0_CAP0_48") (pintype "bidirectional"))
    )
    (net (code "95") (name "unconnected-(IC5-PIO3_4{slash}CT16B0_CAP1{slash}RXD-Pad18)") (class "Default")
      (node (ref "IC5") (pin "18") (pinfunction "PIO3_4/CT16B0_CAP1/RXD_18") (pintype "bidirectional"))
    )
    (net (code "96") (name "unconnected-(IC5-PIO3_5{slash}CT16B1_CAP1{slash}TXD-Pad21)") (class "Default")
      (node (ref "IC5") (pin "21") (pinfunction "PIO3_5/CT16B1_CAP1/TXD_21") (pintype "bidirectional"))
    )
    (net (code "97") (name "unconnected-(IC5-XTALOUT-Pad7)") (class "Default")
      (node (ref "IC5") (pin "7") (pinfunction "XTALOUT_7") (pintype "output"))
    )
    (net (code "98") (name "unconnected-(JP2-5V-Pad2)") (class "Default")
      (node (ref "JP2") (pin "2") (pinfunction "5V_2") (pintype "passive"))
    )
    (net (code "99") (name "unconnected-(JP2-5V-Pad4)") (class "Default")
      (node (ref "JP2") (pin "4") (pinfunction "5V_4") (pintype "passive"))
    )
    (net (code "100") (name "unconnected-(JP2-CE0{slash}IO8-Pad24)") (class "Default")
      (node (ref "JP2") (pin "24") (pinfunction "CE0/IO8_24") (pintype "passive"))
    )
    (net (code "101") (name "unconnected-(JP2-CE1{slash}IO7-Pad26)") (class "Default")
      (node (ref "JP2") (pin "26") (pinfunction "CE1/IO7_26") (pintype "passive"))
    )
    (net (code "102") (name "unconnected-(JP2-IO4-Pad7)") (class "Default")
      (node (ref "JP2") (pin "7") (pinfunction "IO4_7") (pintype "passive"))
    )
    (net (code "103") (name "unconnected-(JP2-IO5-Pad29)") (class "Default")
      (node (ref "JP2") (pin "29") (pinfunction "IO5_29") (pintype "bidirectional"))
    )
    (net (code "104") (name "unconnected-(JP2-IO6-Pad31)") (class "Default")
      (node (ref "JP2") (pin "31") (pinfunction "IO6_31") (pintype "bidirectional"))
    )
    (net (code "105") (name "unconnected-(JP2-IO9{slash}MISO-Pad21)") (class "Default")
      (node (ref "JP2") (pin "21") (pinfunction "IO9/MISO_21") (pintype "passive"))
    )
    (net (code "106") (name "unconnected-(JP2-IO10{slash}MOSI-Pad19)") (class "Default")
      (node (ref "JP2") (pin "19") (pinfunction "IO10/MOSI_19") (pintype "passive"))
    )
    (net (code "107") (name "unconnected-(JP2-IO11{slash}SCK-Pad23)") (class "Default")
      (node (ref "JP2") (pin "23") (pinfunction "IO11/SCK_23") (pintype "passive"))
    )
    (net (code "108") (name "unconnected-(JP2-IO12-Pad32)") (class "Default")
      (node (ref "JP2") (pin "32") (pinfunction "IO12_32") (pintype "bidirectional"))
    )
    (net (code "109") (name "unconnected-(JP2-IO13-Pad33)") (class "Default")
      (node (ref "JP2") (pin "33") (pinfunction "IO13_33") (pintype "bidirectional"))
    )
    (net (code "110") (name "unconnected-(JP2-IO16-Pad36)") (class "Default")
      (node (ref "JP2") (pin "36") (pinfunction "IO16_36") (pintype "bidirectional"))
    )
    (net (code "111") (name "unconnected-(JP2-IO17-Pad11)") (class "Default")
      (node (ref "JP2") (pin "11") (pinfunction "IO17_11") (pintype "passive"))
    )
    (net (code "112") (name "unconnected-(JP2-IO19-Pad35)") (class "Default")
      (node (ref "JP2") (pin "35") (pinfunction "IO19_35") (pintype "bidirectional"))
    )
    (net (code "113") (name "unconnected-(JP2-IO20-Pad38)") (class "Default")
      (node (ref "JP2") (pin "38") (pinfunction "IO20_38") (pintype "bidirectional"))
    )
    (net (code "114") (name "unconnected-(JP2-IO21-Pad40)") (class "Default")
      (node (ref "JP2") (pin "40") (pinfunction "IO21_40") (pintype "bidirectional"))
    )
    (net (code "115") (name "unconnected-(JP2-IO22-Pad15)") (class "Default")
      (node (ref "JP2") (pin "15") (pinfunction "IO22_15") (pintype "passive"))
    )
    (net (code "116") (name "unconnected-(JP2-IO23-Pad16)") (class "Default")
      (node (ref "JP2") (pin "16") (pinfunction "IO23_16") (pintype "passive"))
    )
    (net (code "117") (name "unconnected-(JP2-IO24-Pad18)") (class "Default")
      (node (ref "JP2") (pin "18") (pinfunction "IO24_18") (pintype "passive"))
    )
    (net (code "118") (name "unconnected-(JP2-IO25-Pad22)") (class "Default")
      (node (ref "JP2") (pin "22") (pinfunction "IO25_22") (pintype "passive"))
    )
    (net (code "119") (name "unconnected-(JP2-IO26-Pad37)") (class "Default")
      (node (ref "JP2") (pin "37") (pinfunction "IO26_37") (pintype "bidirectional"))
    )
    (net (code "120") (name "unconnected-(JP2-IO27-Pad13)") (class "Default")
      (node (ref "JP2") (pin "13") (pinfunction "IO27_13") (pintype "passive"))
    )
    (net (code "121") (name "unconnected-(JP2-PWM{slash}IO18-Pad12)") (class "Default")
      (node (ref "JP2") (pin "12") (pinfunction "PWM/IO18_12") (pintype "passive"))
    )
    (net (code "122") (name "unconnected-(JP7-Pad6)") (class "Default")
      (node (ref "JP7") (pin "6") (pinfunction "6_6") (pintype "passive"))
    )
    (net (code "123") (name "unconnected-(JP7-Pad8)") (class "Default")
      (node (ref "JP7") (pin "8") (pinfunction "8_8") (pintype "passive"))
    )
  )
)
